# gate.net
KiCad netlist of a schematic drawn in EAGLE
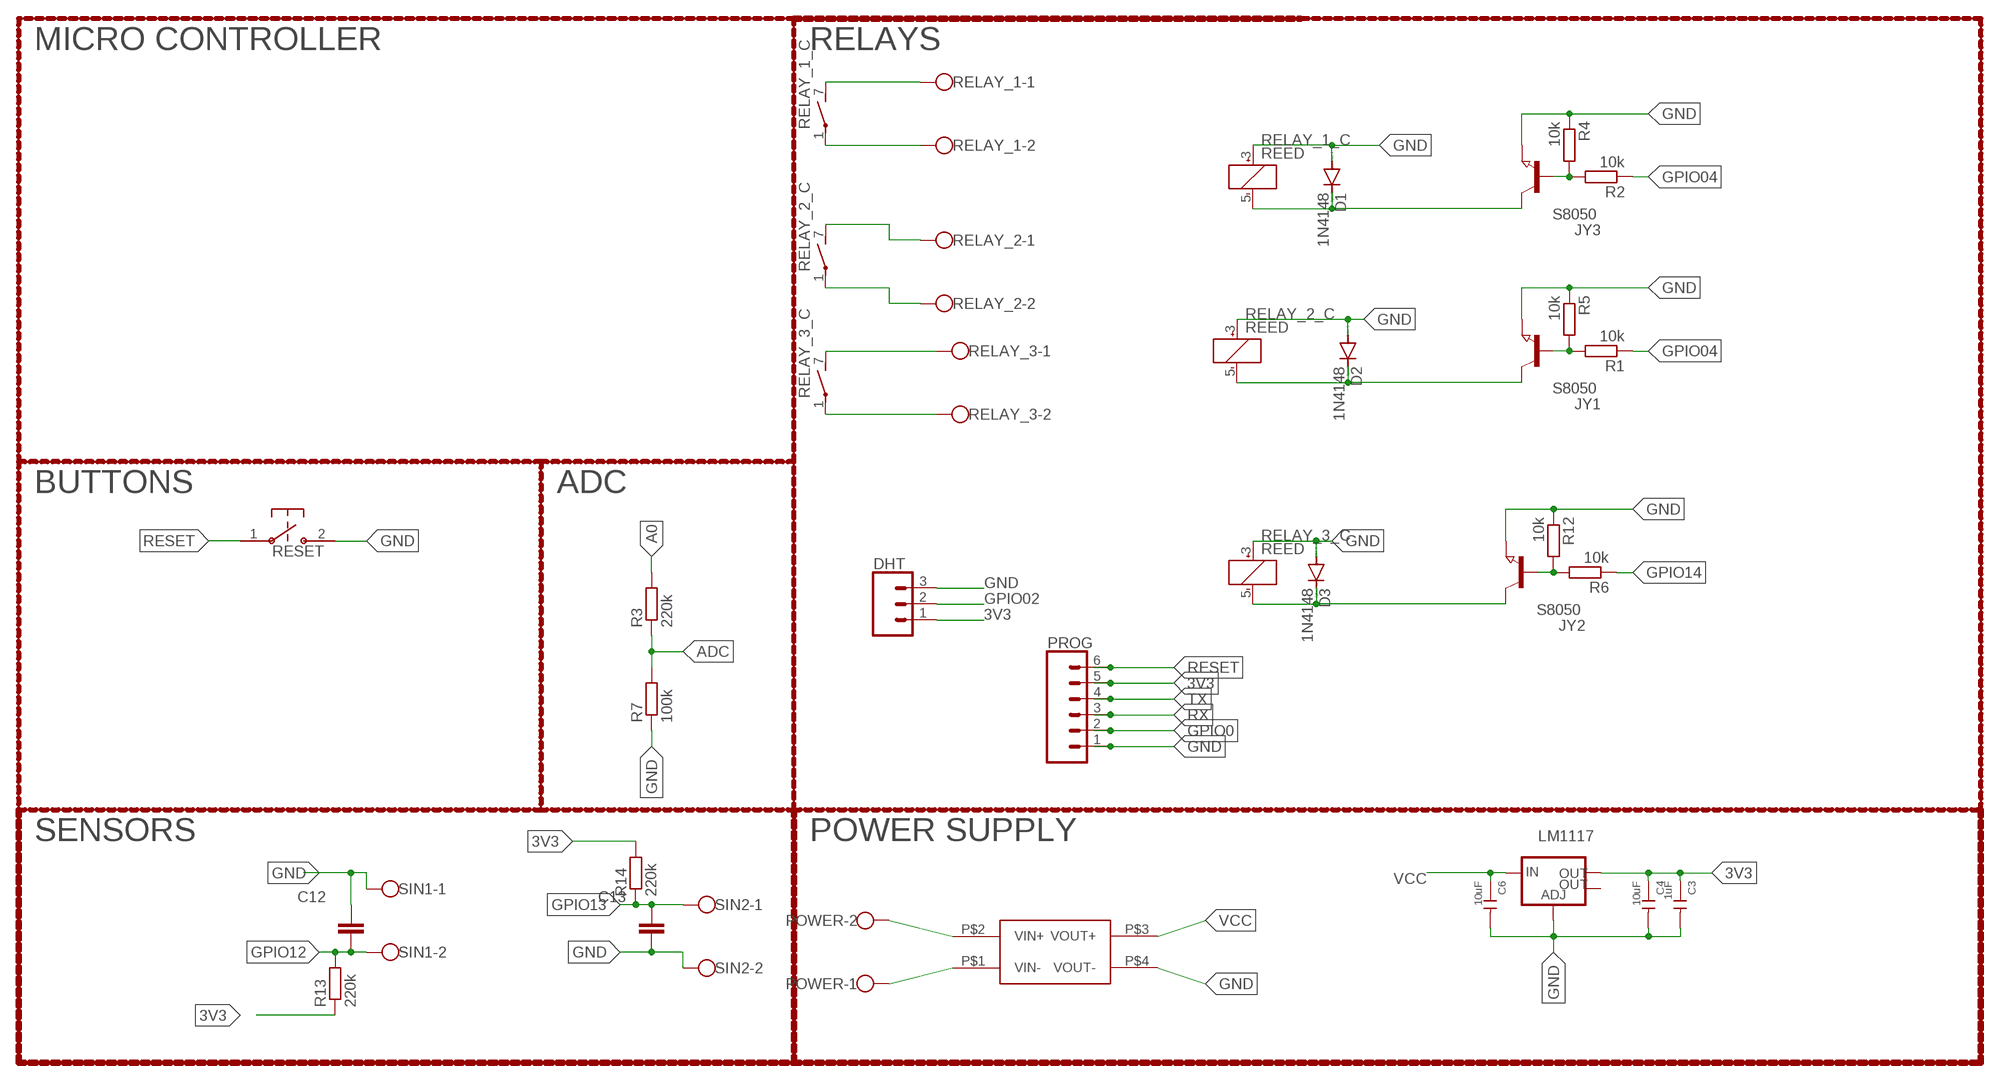
[diagram p0: schematic, sheet 1]

(export (version "E")
  (design (tool "Eeschema 10.0.6"))
  (components
    (comp (ref "AMS1117")
      (value "LM1117")
      (footprint "eagle-import:SOT223")
      (libsource (lib "eagle-import") (part "V_REG_LM1117SOT223"))
    )
    (comp (ref "C3")
      (value "1uF")
      (footprint "eagle-import:C1206")
      (fields (field (name "MPN") "CC1206KKX7RCBB102"))
      (libsource (lib "eagle-import") (part "CERAMIC-1NF-1KV-10%-X7R?(1206)"))
    )
    (comp (ref "C4")
      (value "10uF")
      (footprint "eagle-import:C1206")
      (fields (field (name "MPN") "CC1206KKX7RCBB102"))
      (libsource (lib "eagle-import") (part "CERAMIC-1NF-1KV-10%-X7R?(1206)"))
    )
    (comp (ref "C6")
      (value "10uF")
      (footprint "eagle-import:C1206")
      (fields (field (name "MPN") "CC1206KKX7RCBB102"))
      (libsource (lib "eagle-import") (part "CERAMIC-1NF-1KV-10%-X7R?(1206)"))
    )
    (comp (ref "C12")
      (value "C-EUC0805")
      (footprint "eagle-import:C0805")
      (libsource (lib "eagle-import") (part "C-EUC0805"))
    )
    (comp (ref "C13")
      (value "C-EUC0805")
      (footprint "eagle-import:C0805")
      (libsource (lib "eagle-import") (part "C-EUC0805"))
    )
    (comp (ref "D1")
      (value "1N4148")
      (footprint "eagle-import:SOD80C")
      (libsource (lib "eagle-import") (part "DIODE-SOD80C"))
    )
    (comp (ref "D2")
      (value "1N4148")
      (footprint "eagle-import:SOD80C")
      (libsource (lib "eagle-import") (part "DIODE-SOD80C"))
    )
    (comp (ref "D3")
      (value "1N4148")
      (footprint "eagle-import:SOD80C")
      (libsource (lib "eagle-import") (part "DIODE-SOD80C"))
    )
    (comp (ref "DHT")
      (value "CONN_03")
      (footprint "eagle-import:1X03")
      (libsource (lib "eagle-import") (part "CONN_03"))
    )
    (comp (ref "JY1")
      (value "S8050")
      (footprint "eagle-import:SOT23")
      (libsource (lib "eagle-import") (part "NPN-TRANSISTOR_SOT23"))
    )
    (comp (ref "JY2")
      (value "S8050")
      (footprint "eagle-import:SOT23")
      (libsource (lib "eagle-import") (part "NPN-TRANSISTOR_SOT23"))
    )
    (comp (ref "JY3")
      (value "S8050")
      (footprint "eagle-import:SOT23")
      (libsource (lib "eagle-import") (part "NPN-TRANSISTOR_SOT23"))
    )
    (comp (ref "POWER")
      (value "W237-102")
      (footprint "eagle-import:W237-102")
      (fields (field (name "MPN") "237-102"))
      (libsource (lib "eagle-import") (part "W237-102"))
    )
    (comp (ref "PROG")
      (value "CONN_06NO_SILK_NO_POP")
      (footprint "eagle-import:1X06_NO_SILK")
      (libsource (lib "eagle-import") (part "CONN_06NO_SILK_NO_POP"))
    )
    (comp (ref "R1")
      (value "10k")
      (footprint "eagle-import:R0603")
      (libsource (lib "eagle-import") (part "R-EU_R0603"))
    )
    (comp (ref "R2")
      (value "10k")
      (footprint "eagle-import:R0603")
      (libsource (lib "eagle-import") (part "R-EU_R0603"))
    )
    (comp (ref "R3")
      (value "220k")
      (footprint "eagle-import:R0603")
      (libsource (lib "eagle-import") (part "R-EU_R0603"))
    )
    (comp (ref "R4")
      (value "10k")
      (footprint "eagle-import:R0603")
      (libsource (lib "eagle-import") (part "R-EU_R0603"))
    )
    (comp (ref "R5")
      (value "10k")
      (footprint "eagle-import:R0603")
      (libsource (lib "eagle-import") (part "R-EU_R0603"))
    )
    (comp (ref "R6")
      (value "10k")
      (footprint "eagle-import:R0603")
      (libsource (lib "eagle-import") (part "R-EU_R0603"))
    )
    (comp (ref "R7")
      (value "100k")
      (footprint "eagle-import:R0603")
      (libsource (lib "eagle-import") (part "R-EU_R0603"))
    )
    (comp (ref "R12")
      (value "10k")
      (footprint "eagle-import:R0603")
      (libsource (lib "eagle-import") (part "R-EU_R0603"))
    )
    (comp (ref "R13")
      (value "220k")
      (footprint "eagle-import:R0603")
      (libsource (lib "eagle-import") (part "R-EU_R0603"))
    )
    (comp (ref "R14")
      (value "220k")
      (footprint "eagle-import:R0603")
      (libsource (lib "eagle-import") (part "R-EU_R0603"))
    )
    (comp (ref "RELAY_1")
      (value "W237-102")
      (footprint "eagle-import:W237-102")
      (fields (field (name "MPN") "237-102"))
      (libsource (lib "eagle-import") (part "W237-102"))
    )
    (comp (ref "RELAY_1_C")
      (value "REED")
      (footprint "eagle-import:REED")
      (libsource (lib "eagle-import") (part "REED"))
    )
    (comp (ref "RELAY_2")
      (value "W237-102")
      (footprint "eagle-import:W237-102")
      (fields (field (name "MPN") "237-102"))
      (libsource (lib "eagle-import") (part "W237-102"))
    )
    (comp (ref "RELAY_2_C")
      (value "REED")
      (footprint "eagle-import:REED")
      (libsource (lib "eagle-import") (part "REED"))
    )
    (comp (ref "RELAY_3")
      (value "W237-102")
      (footprint "eagle-import:W237-102")
      (fields (field (name "MPN") "237-102"))
      (libsource (lib "eagle-import") (part "W237-102"))
    )
    (comp (ref "RELAY_3_C")
      (value "REED")
      (footprint "eagle-import:REED")
      (libsource (lib "eagle-import") (part "REED"))
    )
    (comp (ref "RESET")
      (value "B3U-1000P-2P-SMD")
      (footprint "eagle-import:B3U-1000P")
      (fields (field (name "MANUFACTURER") "Omron") (field (name "MPN") "B3U-1000P"))
      (libsource (lib "eagle-import") (part "B3U-1000P"))
    )
    (comp (ref "SIN1")
      (value "W237-102")
      (footprint "eagle-import:W237-102")
      (fields (field (name "MPN") "237-102"))
      (libsource (lib "eagle-import") (part "W237-102"))
    )
    (comp (ref "SIN2")
      (value "W237-102")
      (footprint "eagle-import:W237-102")
      (fields (field (name "MPN") "237-102"))
      (libsource (lib "eagle-import") (part "W237-102"))
    )
    (comp (ref "U$2")
      (value "MP1584-MINI-SMDDL")
      (footprint "eagle-import:MINI-DC-BRICK_DL-SMD")
      (libsource (lib "eagle-import") (part "MP1584-MINI-SMDDL"))
    )
  )
  (nets
    (net (code "1") (name "/GPIO02") (class "Default")
      (node (ref "DHT") (pin "2") (pinfunction "2_2") (pintype "passive"))
    )
    (net (code "2") (name "3V3") (class "Default")
      (node (ref "AMS1117") (pin "2") (pinfunction "OUT_2") (pintype "output"))
      (node (ref "C3") (pin "1") (pinfunction "1_1") (pintype "passive"))
      (node (ref "C4") (pin "1") (pinfunction "1_1") (pintype "passive"))
      (node (ref "DHT") (pin "1") (pinfunction "1_1") (pintype "passive"))
      (node (ref "PROG") (pin "5") (pinfunction "5_5") (pintype "passive"))
      (node (ref "R13") (pin "1") (pinfunction "1_1") (pintype "passive"))
      (node (ref "R14") (pin "2") (pinfunction "2_2") (pintype "passive"))
    )
    (net (code "3") (name "A0") (class "Default")
      (node (ref "R3") (pin "2") (pinfunction "2_2") (pintype "passive"))
    )
    (net (code "4") (name "ADC") (class "Default")
      (node (ref "R3") (pin "1") (pinfunction "1_1") (pintype "passive"))
      (node (ref "R7") (pin "2") (pinfunction "2_2") (pintype "passive"))
    )
    (net (code "5") (name "GND") (class "Default")
      (node (ref "AMS1117") (pin "1") (pinfunction "ADJ_1") (pintype "input"))
      (node (ref "C12") (pin "1") (pinfunction "1_1") (pintype "passive"))
      (node (ref "C13") (pin "2") (pinfunction "2_2") (pintype "passive"))
      (node (ref "C3") (pin "2") (pinfunction "2_2") (pintype "passive"))
      (node (ref "C4") (pin "2") (pinfunction "2_2") (pintype "passive"))
      (node (ref "C6") (pin "2") (pinfunction "2_2") (pintype "passive"))
      (node (ref "D1") (pin "A") (pinfunction "A_A") (pintype "passive"))
      (node (ref "D2") (pin "A") (pinfunction "A_A") (pintype "passive"))
      (node (ref "D3") (pin "A") (pinfunction "A_A") (pintype "passive"))
      (node (ref "DHT") (pin "3") (pinfunction "3_3") (pintype "passive"))
      (node (ref "JY1") (pin "2") (pinfunction "E_2") (pintype "passive"))
      (node (ref "JY2") (pin "2") (pinfunction "E_2") (pintype "passive"))
      (node (ref "JY3") (pin "2") (pinfunction "E_2") (pintype "passive"))
      (node (ref "POWER") (pin "1") (pinfunction "KL_1") (pintype "passive"))
      (node (ref "PROG") (pin "1") (pinfunction "1_1") (pintype "passive"))
      (node (ref "R12") (pin "1") (pinfunction "1_1") (pintype "passive"))
      (node (ref "R4") (pin "1") (pinfunction "1_1") (pintype "passive"))
      (node (ref "R5") (pin "1") (pinfunction "1_1") (pintype "passive"))
      (node (ref "R7") (pin "1") (pinfunction "1_1") (pintype "passive"))
      (node (ref "RELAY_1_C") (pin "3") (pinfunction "+_3") (pintype "passive"))
      (node (ref "RELAY_2_C") (pin "3") (pinfunction "+_3") (pintype "passive"))
      (node (ref "RELAY_3_C") (pin "3") (pinfunction "+_3") (pintype "passive"))
      (node (ref "RESET") (pin "2") (pinfunction "P$2_2") (pintype "passive"))
      (node (ref "SIN1") (pin "1") (pinfunction "KL_1") (pintype "passive"))
      (node (ref "SIN2") (pin "2") (pinfunction "KL_2") (pintype "passive"))
      (node (ref "U$2") (pin "P$1") (pinfunction "VIN-_P$1") (pintype "input"))
      (node (ref "U$2") (pin "P$4") (pinfunction "VOUT-_P$4") (pintype "output"))
    )
    (net (code "6") (name "GPIO0") (class "Default")
      (node (ref "PROG") (pin "2") (pinfunction "2_2") (pintype "passive"))
    )
    (net (code "7") (name "GPIO04") (class "Default")
      (node (ref "R1") (pin "1") (pinfunction "1_1") (pintype "passive"))
      (node (ref "R2") (pin "1") (pinfunction "1_1") (pintype "passive"))
    )
    (net (code "8") (name "GPIO12") (class "Default")
      (node (ref "C12") (pin "2") (pinfunction "2_2") (pintype "passive"))
      (node (ref "R13") (pin "2") (pinfunction "2_2") (pintype "passive"))
      (node (ref "SIN1") (pin "2") (pinfunction "KL_2") (pintype "passive"))
    )
    (net (code "9") (name "GPIO13") (class "Default")
      (node (ref "C13") (pin "1") (pinfunction "1_1") (pintype "passive"))
      (node (ref "R14") (pin "1") (pinfunction "1_1") (pintype "passive"))
      (node (ref "SIN2") (pin "1") (pinfunction "KL_1") (pintype "passive"))
    )
    (net (code "10") (name "GPIO14") (class "Default")
      (node (ref "R6") (pin "1") (pinfunction "1_1") (pintype "passive"))
    )
    (net (code "11") (name "Net-(JY1-B)") (class "Default")
      (node (ref "JY1") (pin "1") (pinfunction "B_1") (pintype "passive"))
      (node (ref "R1") (pin "2") (pinfunction "2_2") (pintype "passive"))
      (node (ref "R5") (pin "2") (pinfunction "2_2") (pintype "passive"))
    )
    (net (code "12") (name "Net-(JY1-C)") (class "Default")
      (node (ref "D2") (pin "C") (pinfunction "C_C") (pintype "passive"))
      (node (ref "JY1") (pin "3") (pinfunction "C_3") (pintype "passive"))
      (node (ref "RELAY_2_C") (pin "5") (pinfunction "-_5") (pintype "passive"))
    )
    (net (code "13") (name "Net-(JY2-B)") (class "Default")
      (node (ref "JY2") (pin "1") (pinfunction "B_1") (pintype "passive"))
      (node (ref "R12") (pin "2") (pinfunction "2_2") (pintype "passive"))
      (node (ref "R6") (pin "2") (pinfunction "2_2") (pintype "passive"))
    )
    (net (code "14") (name "Net-(JY2-C)") (class "Default")
      (node (ref "D3") (pin "C") (pinfunction "C_C") (pintype "passive"))
      (node (ref "JY2") (pin "3") (pinfunction "C_3") (pintype "passive"))
      (node (ref "RELAY_3_C") (pin "5") (pinfunction "-_5") (pintype "passive"))
    )
    (net (code "15") (name "Net-(JY3-B)") (class "Default")
      (node (ref "JY3") (pin "1") (pinfunction "B_1") (pintype "passive"))
      (node (ref "R2") (pin "2") (pinfunction "2_2") (pintype "passive"))
      (node (ref "R4") (pin "2") (pinfunction "2_2") (pintype "passive"))
    )
    (net (code "16") (name "Net-(JY3-C)") (class "Default")
      (node (ref "D1") (pin "C") (pinfunction "C_C") (pintype "passive"))
      (node (ref "JY3") (pin "3") (pinfunction "C_3") (pintype "passive"))
      (node (ref "RELAY_1_C") (pin "5") (pinfunction "-_5") (pintype "passive"))
    )
    (net (code "17") (name "Net-(POWERB-KL)") (class "Default")
      (node (ref "POWER") (pin "2") (pinfunction "KL_2") (pintype "passive"))
      (node (ref "U$2") (pin "P$2") (pinfunction "VIN+_P$2") (pintype "input"))
    )
    (net (code "18") (name "Net-(RELAY_1A-KL)") (class "Default")
      (node (ref "RELAY_1") (pin "1") (pinfunction "KL_1") (pintype "passive"))
      (node (ref "RELAY_1_C") (pin "7") (pinfunction "S_7") (pintype "passive"))
    )
    (net (code "19") (name "Net-(RELAY_1B-KL)") (class "Default")
      (node (ref "RELAY_1") (pin "2") (pinfunction "KL_2") (pintype "passive"))
      (node (ref "RELAY_1_C") (pin "1") (pinfunction "P_1") (pintype "passive"))
    )
    (net (code "20") (name "Net-(RELAY_2A-KL)") (class "Default")
      (node (ref "RELAY_2") (pin "1") (pinfunction "KL_1") (pintype "passive"))
      (node (ref "RELAY_2_C") (pin "7") (pinfunction "S_7") (pintype "passive"))
    )
    (net (code "21") (name "Net-(RELAY_2B-KL)") (class "Default")
      (node (ref "RELAY_2") (pin "2") (pinfunction "KL_2") (pintype "passive"))
      (node (ref "RELAY_2_C") (pin "1") (pinfunction "P_1") (pintype "passive"))
    )
    (net (code "22") (name "Net-(RELAY_3A-KL)") (class "Default")
      (node (ref "RELAY_3") (pin "1") (pinfunction "KL_1") (pintype "passive"))
      (node (ref "RELAY_3_C") (pin "7") (pinfunction "S_7") (pintype "passive"))
    )
    (net (code "23") (name "Net-(RELAY_3B-KL)") (class "Default")
      (node (ref "RELAY_3") (pin "2") (pinfunction "KL_2") (pintype "passive"))
      (node (ref "RELAY_3_C") (pin "1") (pinfunction "P_1") (pintype "passive"))
    )
    (net (code "24") (name "RESET") (class "Default")
      (node (ref "PROG") (pin "6") (pinfunction "6_6") (pintype "passive"))
      (node (ref "RESET") (pin "1") (pinfunction "P$1_1") (pintype "passive"))
    )
    (net (code "25") (name "RX") (class "Default")
      (node (ref "PROG") (pin "3") (pinfunction "3_3") (pintype "passive"))
    )
    (net (code "26") (name "TX") (class "Default")
      (node (ref "PROG") (pin "4") (pinfunction "4_4") (pintype "passive"))
    )
    (net (code "27") (name "VCC") (class "Default")
      (node (ref "AMS1117") (pin "3") (pinfunction "IN_3") (pintype "input"))
      (node (ref "C6") (pin "1") (pinfunction "1_1") (pintype "passive"))
      (node (ref "U$2") (pin "P$3") (pinfunction "VOUT+_P$3") (pintype "output"))
    )
    (net (code "28") (name "unconnected-(AMS1117-OUT-Pad4)") (class "Default")
      (node (ref "AMS1117") (pin "4") (pinfunction "OUT_4") (pintype "output"))
    )
  )
)
